# eurorack-passive-vca.net
KiCad netlist of a schematic drawn in EAGLE
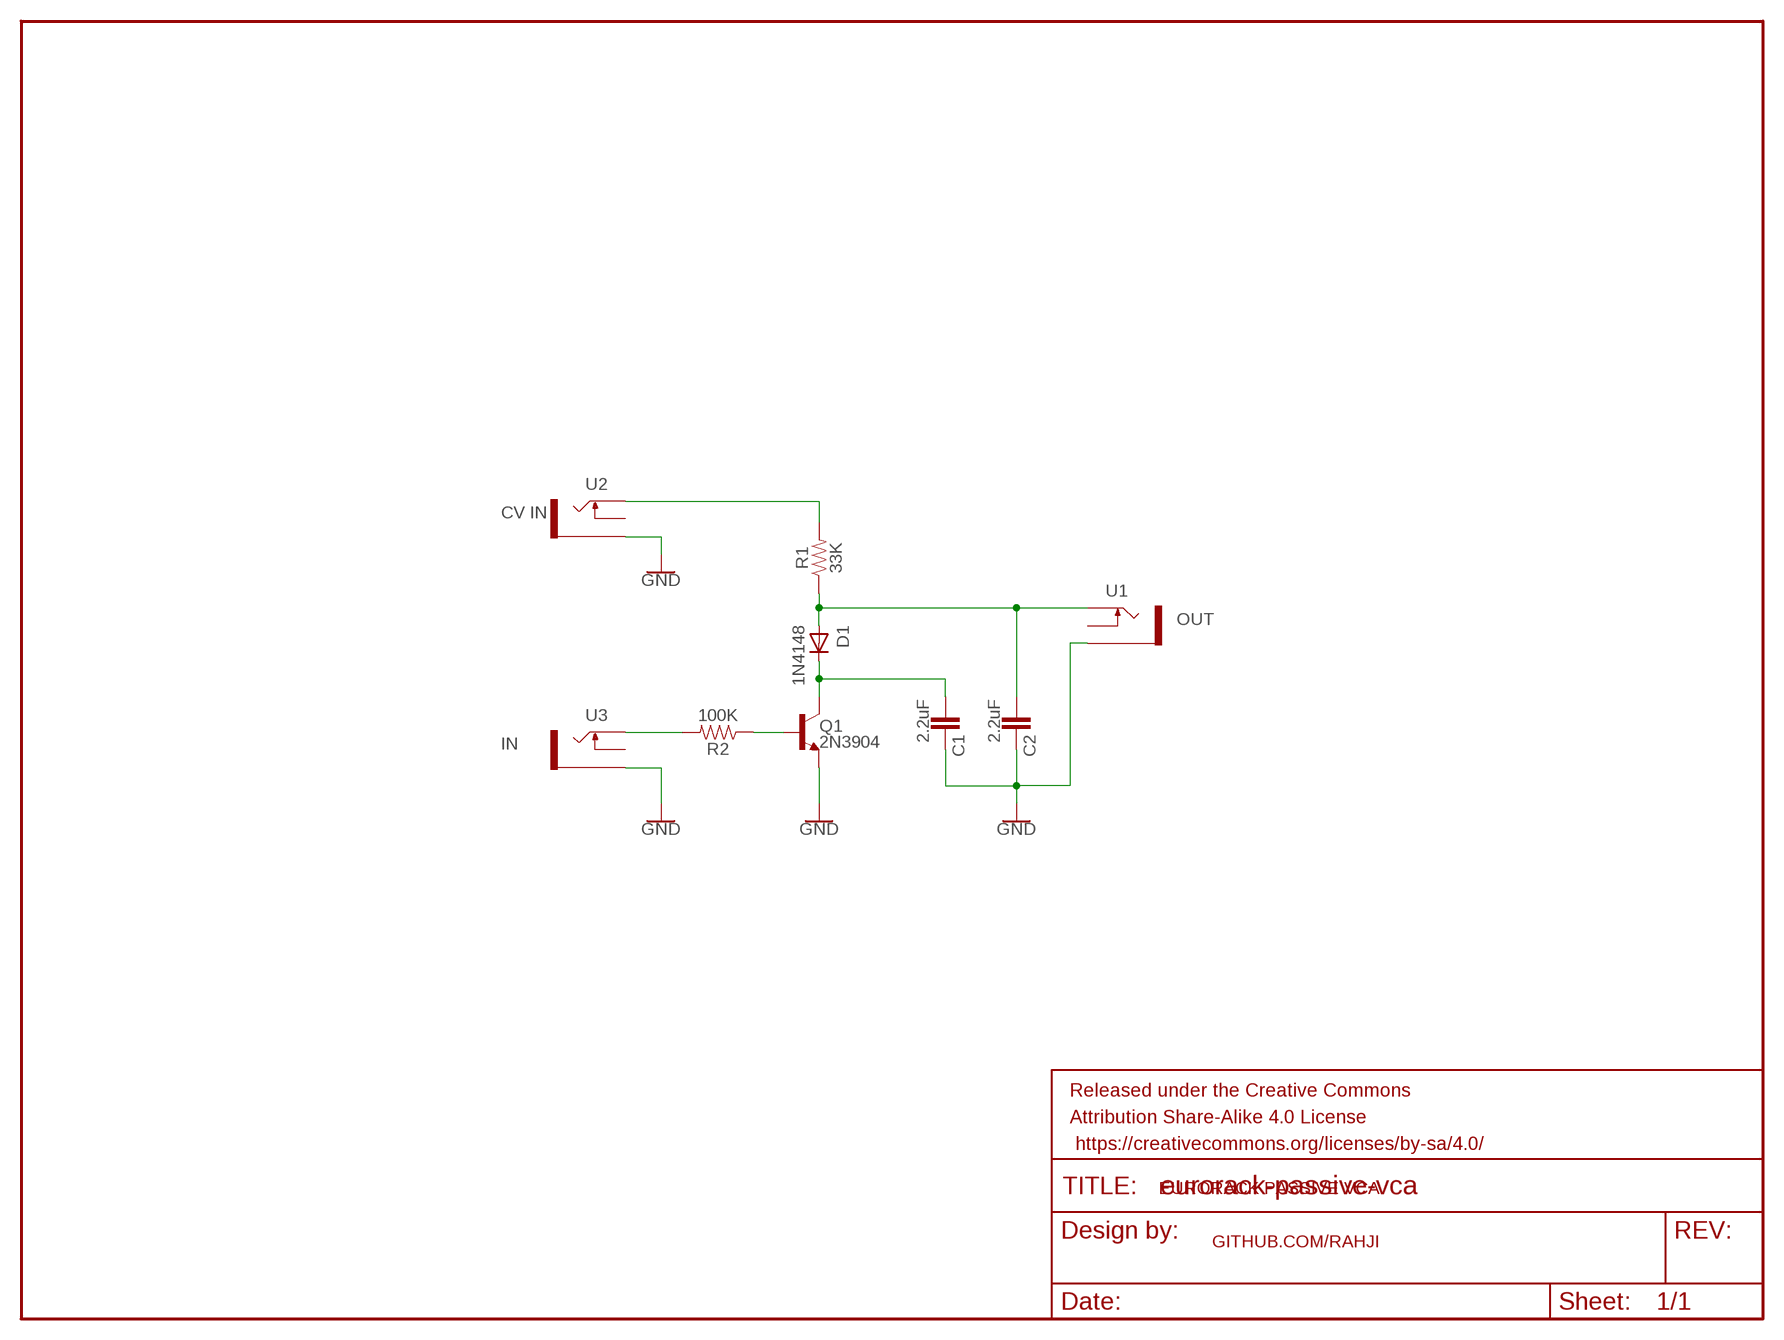
[diagram p0: schematic, sheet 1]

(export (version "E")
  (design (tool "Eeschema 10.0.6"))
  (components
    (comp (ref "C1")
      (value "2.2uF")
      (footprint "eagle-import:CAP-PTH-2.54")
      (libsource (lib "eagle-import") (part "22PF-PTH-2.54MM-200V-5%"))
    )
    (comp (ref "C2")
      (value "2.2uF")
      (footprint "eagle-import:CAP-PTH-2.54")
      (libsource (lib "eagle-import") (part "22PF-PTH-2.54MM-200V-5%"))
    )
    (comp (ref "D1")
      (value "1N4148")
      (footprint "eagle-import:DO-1N4148")
      (libsource (lib "eagle-import") (part "DIODEDO-1N4148"))
    )
    (comp (ref "FRAME1")
      (value "FRAME-LETTERNO_PACKAGE")
      (footprint "eagle-import:DUMMY")
      (fields (field (name "DESIGNER") "Nobody"))
      (libsource (lib "eagle-import") (part "FRAME-LETTERNO_PACKAGE"))
    )
    (comp (ref "Q1")
      (value "2N3904")
      (footprint "eagle-import:TO-92")
      (libsource (lib "eagle-import") (part "TRANS_NPN-2N3904"))
    )
    (comp (ref "R1")
      (value "33K")
      (footprint "eagle-import:AXIAL-0.3")
      (libsource (lib "eagle-import") (part "100OHM-HORIZ-1/4W-1%"))
    )
    (comp (ref "R2")
      (value "100K")
      (footprint "eagle-import:AXIAL-0.3")
      (libsource (lib "eagle-import") (part "100OHM-HORIZ-1/4W-1%"))
    )
    (comp (ref "U1")
      (value "OUT")
      (footprint "eagle-import:WQP-PJ301M-12_JACK")
      (libsource (lib "eagle-import") (part "THONKICONNNEW"))
    )
    (comp (ref "U2")
      (value "CV IN")
      (footprint "eagle-import:WQP-PJ301M-12_JACK")
      (libsource (lib "eagle-import") (part "THONKICONNNEW"))
    )
    (comp (ref "U3")
      (value "IN")
      (footprint "eagle-import:WQP-PJ301M-12_JACK")
      (libsource (lib "eagle-import") (part "THONKICONNNEW"))
    )
  )
  (nets
    (net (code "1") (name "GND") (class "Default")
      (node (ref "C1") (pin "1") (pinfunction "1_1") (pintype "passive"))
      (node (ref "C2") (pin "1") (pinfunction "1_1") (pintype "passive"))
      (node (ref "Q1") (pin "1") (pinfunction "E_1") (pintype "passive"))
      (node (ref "U1") (pin "P$3_SLEEVE") (pinfunction "SLEEVE_P$3_SLEEVE") (pintype "passive"))
      (node (ref "U2") (pin "P$3_SLEEVE") (pinfunction "SLEEVE_P$3_SLEEVE") (pintype "passive"))
      (node (ref "U3") (pin "P$3_SLEEVE") (pinfunction "SLEEVE_P$3_SLEEVE") (pintype "passive"))
    )
    (net (code "2") (name "Net-(Q1-B)") (class "Default")
      (node (ref "Q1") (pin "2") (pinfunction "B_2") (pintype "passive"))
      (node (ref "R2") (pin "P$1") (pinfunction "1_P$1") (pintype "passive"))
    )
    (net (code "3") (name "Net-(Q1-C)") (class "Default")
      (node (ref "C1") (pin "2") (pinfunction "2_2") (pintype "passive"))
      (node (ref "D1") (pin "C") (pinfunction "C_C") (pintype "passive"))
      (node (ref "Q1") (pin "3") (pinfunction "C_3") (pintype "passive"))
    )
    (net (code "4") (name "Net-(R1-1)") (class "Default")
      (node (ref "C2") (pin "2") (pinfunction "2_2") (pintype "passive"))
      (node (ref "D1") (pin "A") (pinfunction "A_A") (pintype "passive"))
      (node (ref "R1") (pin "P$1") (pinfunction "1_P$1") (pintype "passive"))
      (node (ref "U1") (pin "P$1_TIP") (pinfunction "TIP_P$1_TIP") (pintype "passive"))
    )
    (net (code "5") (name "Net-(R1-2)") (class "Default")
      (node (ref "R1") (pin "P$2") (pinfunction "2_P$2") (pintype "passive"))
      (node (ref "U2") (pin "P$1_TIP") (pinfunction "TIP_P$1_TIP") (pintype "passive"))
    )
    (net (code "6") (name "Net-(R2-2)") (class "Default")
      (node (ref "R2") (pin "P$2") (pinfunction "2_P$2") (pintype "passive"))
      (node (ref "U3") (pin "P$1_TIP") (pinfunction "TIP_P$1_TIP") (pintype "passive"))
    )
    (net (code "7") (name "unconnected-(U1-SWITCH-PadP$2_SWITCH)") (class "Default")
      (node (ref "U1") (pin "P$2_SWITCH") (pinfunction "SWITCH_P$2_SWITCH") (pintype "passive"))
    )
    (net (code "8") (name "unconnected-(U2-SWITCH-PadP$2_SWITCH)") (class "Default")
      (node (ref "U2") (pin "P$2_SWITCH") (pinfunction "SWITCH_P$2_SWITCH") (pintype "passive"))
    )
    (net (code "9") (name "unconnected-(U3-SWITCH-PadP$2_SWITCH)") (class "Default")
      (node (ref "U3") (pin "P$2_SWITCH") (pinfunction "SWITCH_P$2_SWITCH") (pintype "passive"))
    )
  )
)
